# BreakoutIcosaStellaOval.net
KiCad netlist of a schematic drawn in EAGLE
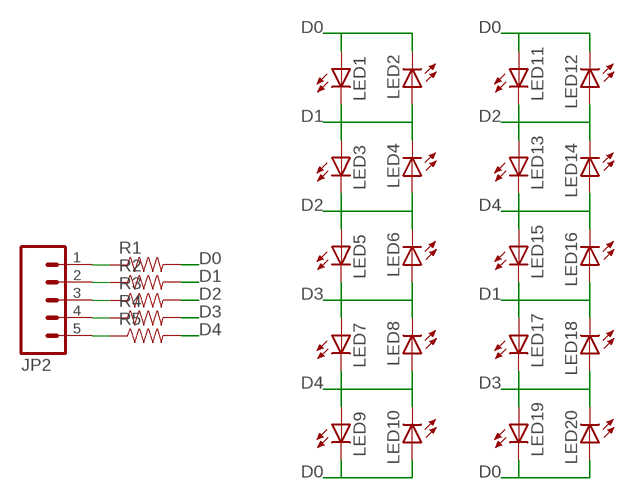
[diagram p0: schematic, sheet 1]

(export (version "E")
  (design (tool "Eeschema 10.0.6"))
  (components
    (comp (ref "JP2")
      (value "M05PTH")
      (footprint "eagle-import:1X05")
      (libsource (lib "eagle-import") (part "M05PTH"))
    )
    (comp (ref "LED1")
      (value "LEDOVAL")
      (footprint "eagle-import:LED-OVAL")
      (libsource (lib "eagle-import") (part "LEDOVAL"))
    )
    (comp (ref "LED2")
      (value "LEDOVAL")
      (footprint "eagle-import:LED-OVAL")
      (libsource (lib "eagle-import") (part "LEDOVAL"))
    )
    (comp (ref "LED3")
      (value "LEDOVAL")
      (footprint "eagle-import:LED-OVAL")
      (libsource (lib "eagle-import") (part "LEDOVAL"))
    )
    (comp (ref "LED4")
      (value "LEDOVAL")
      (footprint "eagle-import:LED-OVAL")
      (libsource (lib "eagle-import") (part "LEDOVAL"))
    )
    (comp (ref "LED5")
      (value "LEDOVAL")
      (footprint "eagle-import:LED-OVAL")
      (libsource (lib "eagle-import") (part "LEDOVAL"))
    )
    (comp (ref "LED6")
      (value "LEDOVAL")
      (footprint "eagle-import:LED-OVAL")
      (libsource (lib "eagle-import") (part "LEDOVAL"))
    )
    (comp (ref "LED7")
      (value "LEDOVAL")
      (footprint "eagle-import:LED-OVAL")
      (libsource (lib "eagle-import") (part "LEDOVAL"))
    )
    (comp (ref "LED8")
      (value "LEDOVAL")
      (footprint "eagle-import:LED-OVAL")
      (libsource (lib "eagle-import") (part "LEDOVAL"))
    )
    (comp (ref "LED9")
      (value "LEDOVAL")
      (footprint "eagle-import:LED-OVAL")
      (libsource (lib "eagle-import") (part "LEDOVAL"))
    )
    (comp (ref "LED10")
      (value "LEDOVAL")
      (footprint "eagle-import:LED-OVAL")
      (libsource (lib "eagle-import") (part "LEDOVAL"))
    )
    (comp (ref "LED11")
      (value "LEDOVAL")
      (footprint "eagle-import:LED-OVAL")
      (libsource (lib "eagle-import") (part "LEDOVAL"))
    )
    (comp (ref "LED12")
      (value "LEDOVAL")
      (footprint "eagle-import:LED-OVAL")
      (libsource (lib "eagle-import") (part "LEDOVAL"))
    )
    (comp (ref "LED13")
      (value "LEDOVAL")
      (footprint "eagle-import:LED-OVAL")
      (libsource (lib "eagle-import") (part "LEDOVAL"))
    )
    (comp (ref "LED14")
      (value "LEDOVAL")
      (footprint "eagle-import:LED-OVAL")
      (libsource (lib "eagle-import") (part "LEDOVAL"))
    )
    (comp (ref "LED15")
      (value "LEDOVAL")
      (footprint "eagle-import:LED-OVAL")
      (libsource (lib "eagle-import") (part "LEDOVAL"))
    )
    (comp (ref "LED16")
      (value "LEDOVAL")
      (footprint "eagle-import:LED-OVAL")
      (libsource (lib "eagle-import") (part "LEDOVAL"))
    )
    (comp (ref "LED17")
      (value "LEDOVAL")
      (footprint "eagle-import:LED-OVAL")
      (libsource (lib "eagle-import") (part "LEDOVAL"))
    )
    (comp (ref "LED18")
      (value "LEDOVAL")
      (footprint "eagle-import:LED-OVAL")
      (libsource (lib "eagle-import") (part "LEDOVAL"))
    )
    (comp (ref "LED19")
      (value "LEDOVAL")
      (footprint "eagle-import:LED-OVAL")
      (libsource (lib "eagle-import") (part "LEDOVAL"))
    )
    (comp (ref "LED20")
      (value "LEDOVAL")
      (footprint "eagle-import:LED-OVAL")
      (libsource (lib "eagle-import") (part "LEDOVAL"))
    )
    (comp (ref "R1")
      (value "RESISTORAXIAL-0.3")
      (footprint "eagle-import:AXIAL-0.3")
      (libsource (lib "eagle-import") (part "RESISTORAXIAL-0.3"))
    )
    (comp (ref "R2")
      (value "RESISTORAXIAL-0.3")
      (footprint "eagle-import:AXIAL-0.3")
      (libsource (lib "eagle-import") (part "RESISTORAXIAL-0.3"))
    )
    (comp (ref "R3")
      (value "RESISTORAXIAL-0.3")
      (footprint "eagle-import:AXIAL-0.3")
      (libsource (lib "eagle-import") (part "RESISTORAXIAL-0.3"))
    )
    (comp (ref "R4")
      (value "RESISTORAXIAL-0.3")
      (footprint "eagle-import:AXIAL-0.3")
      (libsource (lib "eagle-import") (part "RESISTORAXIAL-0.3"))
    )
    (comp (ref "R5")
      (value "RESISTORAXIAL-0.3")
      (footprint "eagle-import:AXIAL-0.3")
      (libsource (lib "eagle-import") (part "RESISTORAXIAL-0.3"))
    )
  )
  (nets
    (net (code "1") (name "/D0") (class "Default")
      (node (ref "LED1") (pin "ANODE") (pinfunction "A_ANODE") (pintype "passive"))
      (node (ref "LED10") (pin "ANODE") (pinfunction "A_ANODE") (pintype "passive"))
      (node (ref "LED11") (pin "ANODE") (pinfunction "A_ANODE") (pintype "passive"))
      (node (ref "LED12") (pin "CATHODE") (pinfunction "C_CATHODE") (pintype "passive"))
      (node (ref "LED19") (pin "CATHODE") (pinfunction "C_CATHODE") (pintype "passive"))
      (node (ref "LED2") (pin "CATHODE") (pinfunction "C_CATHODE") (pintype "passive"))
      (node (ref "LED20") (pin "ANODE") (pinfunction "A_ANODE") (pintype "passive"))
      (node (ref "LED9") (pin "CATHODE") (pinfunction "C_CATHODE") (pintype "passive"))
      (node (ref "R1") (pin "P$2") (pinfunction "2_P$2") (pintype "passive"))
    )
    (net (code "2") (name "/D1") (class "Default")
      (node (ref "LED1") (pin "CATHODE") (pinfunction "C_CATHODE") (pintype "passive"))
      (node (ref "LED15") (pin "CATHODE") (pinfunction "C_CATHODE") (pintype "passive"))
      (node (ref "LED16") (pin "ANODE") (pinfunction "A_ANODE") (pintype "passive"))
      (node (ref "LED17") (pin "ANODE") (pinfunction "A_ANODE") (pintype "passive"))
      (node (ref "LED18") (pin "CATHODE") (pinfunction "C_CATHODE") (pintype "passive"))
      (node (ref "LED2") (pin "ANODE") (pinfunction "A_ANODE") (pintype "passive"))
      (node (ref "LED3") (pin "ANODE") (pinfunction "A_ANODE") (pintype "passive"))
      (node (ref "LED4") (pin "CATHODE") (pinfunction "C_CATHODE") (pintype "passive"))
      (node (ref "R2") (pin "P$2") (pinfunction "2_P$2") (pintype "passive"))
    )
    (net (code "3") (name "/D2") (class "Default")
      (node (ref "LED11") (pin "CATHODE") (pinfunction "C_CATHODE") (pintype "passive"))
      (node (ref "LED12") (pin "ANODE") (pinfunction "A_ANODE") (pintype "passive"))
      (node (ref "LED13") (pin "ANODE") (pinfunction "A_ANODE") (pintype "passive"))
      (node (ref "LED14") (pin "CATHODE") (pinfunction "C_CATHODE") (pintype "passive"))
      (node (ref "LED3") (pin "CATHODE") (pinfunction "C_CATHODE") (pintype "passive"))
      (node (ref "LED4") (pin "ANODE") (pinfunction "A_ANODE") (pintype "passive"))
      (node (ref "LED5") (pin "ANODE") (pinfunction "A_ANODE") (pintype "passive"))
      (node (ref "LED6") (pin "CATHODE") (pinfunction "C_CATHODE") (pintype "passive"))
      (node (ref "R3") (pin "P$2") (pinfunction "2_P$2") (pintype "passive"))
    )
    (net (code "4") (name "/D3") (class "Default")
      (node (ref "LED17") (pin "CATHODE") (pinfunction "C_CATHODE") (pintype "passive"))
      (node (ref "LED18") (pin "ANODE") (pinfunction "A_ANODE") (pintype "passive"))
      (node (ref "LED19") (pin "ANODE") (pinfunction "A_ANODE") (pintype "passive"))
      (node (ref "LED20") (pin "CATHODE") (pinfunction "C_CATHODE") (pintype "passive"))
      (node (ref "LED5") (pin "CATHODE") (pinfunction "C_CATHODE") (pintype "passive"))
      (node (ref "LED6") (pin "ANODE") (pinfunction "A_ANODE") (pintype "passive"))
      (node (ref "LED7") (pin "ANODE") (pinfunction "A_ANODE") (pintype "passive"))
      (node (ref "LED8") (pin "CATHODE") (pinfunction "C_CATHODE") (pintype "passive"))
      (node (ref "R4") (pin "P$2") (pinfunction "2_P$2") (pintype "passive"))
    )
    (net (code "5") (name "/D4") (class "Default")
      (node (ref "LED10") (pin "CATHODE") (pinfunction "C_CATHODE") (pintype "passive"))
      (node (ref "LED13") (pin "CATHODE") (pinfunction "C_CATHODE") (pintype "passive"))
      (node (ref "LED14") (pin "ANODE") (pinfunction "A_ANODE") (pintype "passive"))
      (node (ref "LED15") (pin "ANODE") (pinfunction "A_ANODE") (pintype "passive"))
      (node (ref "LED16") (pin "CATHODE") (pinfunction "C_CATHODE") (pintype "passive"))
      (node (ref "LED7") (pin "CATHODE") (pinfunction "C_CATHODE") (pintype "passive"))
      (node (ref "LED8") (pin "ANODE") (pinfunction "A_ANODE") (pintype "passive"))
      (node (ref "LED9") (pin "ANODE") (pinfunction "A_ANODE") (pintype "passive"))
      (node (ref "R5") (pin "P$2") (pinfunction "2_P$2") (pintype "passive"))
    )
    (net (code "6") (name "Net-(R1-1)") (class "Default")
      (node (ref "JP2") (pin "1") (pinfunction "1_1") (pintype "passive"))
      (node (ref "R1") (pin "P$1") (pinfunction "1_P$1") (pintype "passive"))
    )
    (net (code "7") (name "Net-(R2-1)") (class "Default")
      (node (ref "JP2") (pin "2") (pinfunction "2_2") (pintype "passive"))
      (node (ref "R2") (pin "P$1") (pinfunction "1_P$1") (pintype "passive"))
    )
    (net (code "8") (name "Net-(R3-1)") (class "Default")
      (node (ref "JP2") (pin "3") (pinfunction "3_3") (pintype "passive"))
      (node (ref "R3") (pin "P$1") (pinfunction "1_P$1") (pintype "passive"))
    )
    (net (code "9") (name "Net-(R4-1)") (class "Default")
      (node (ref "JP2") (pin "4") (pinfunction "4_4") (pintype "passive"))
      (node (ref "R4") (pin "P$1") (pinfunction "1_P$1") (pintype "passive"))
    )
    (net (code "10") (name "Net-(R5-1)") (class "Default")
      (node (ref "JP2") (pin "5") (pinfunction "5_5") (pintype "passive"))
      (node (ref "R5") (pin "P$1") (pinfunction "1_P$1") (pintype "passive"))
    )
  )
)
